# MCU_OLED.net
KiCad netlist of a schematic drawn in Altium Designer
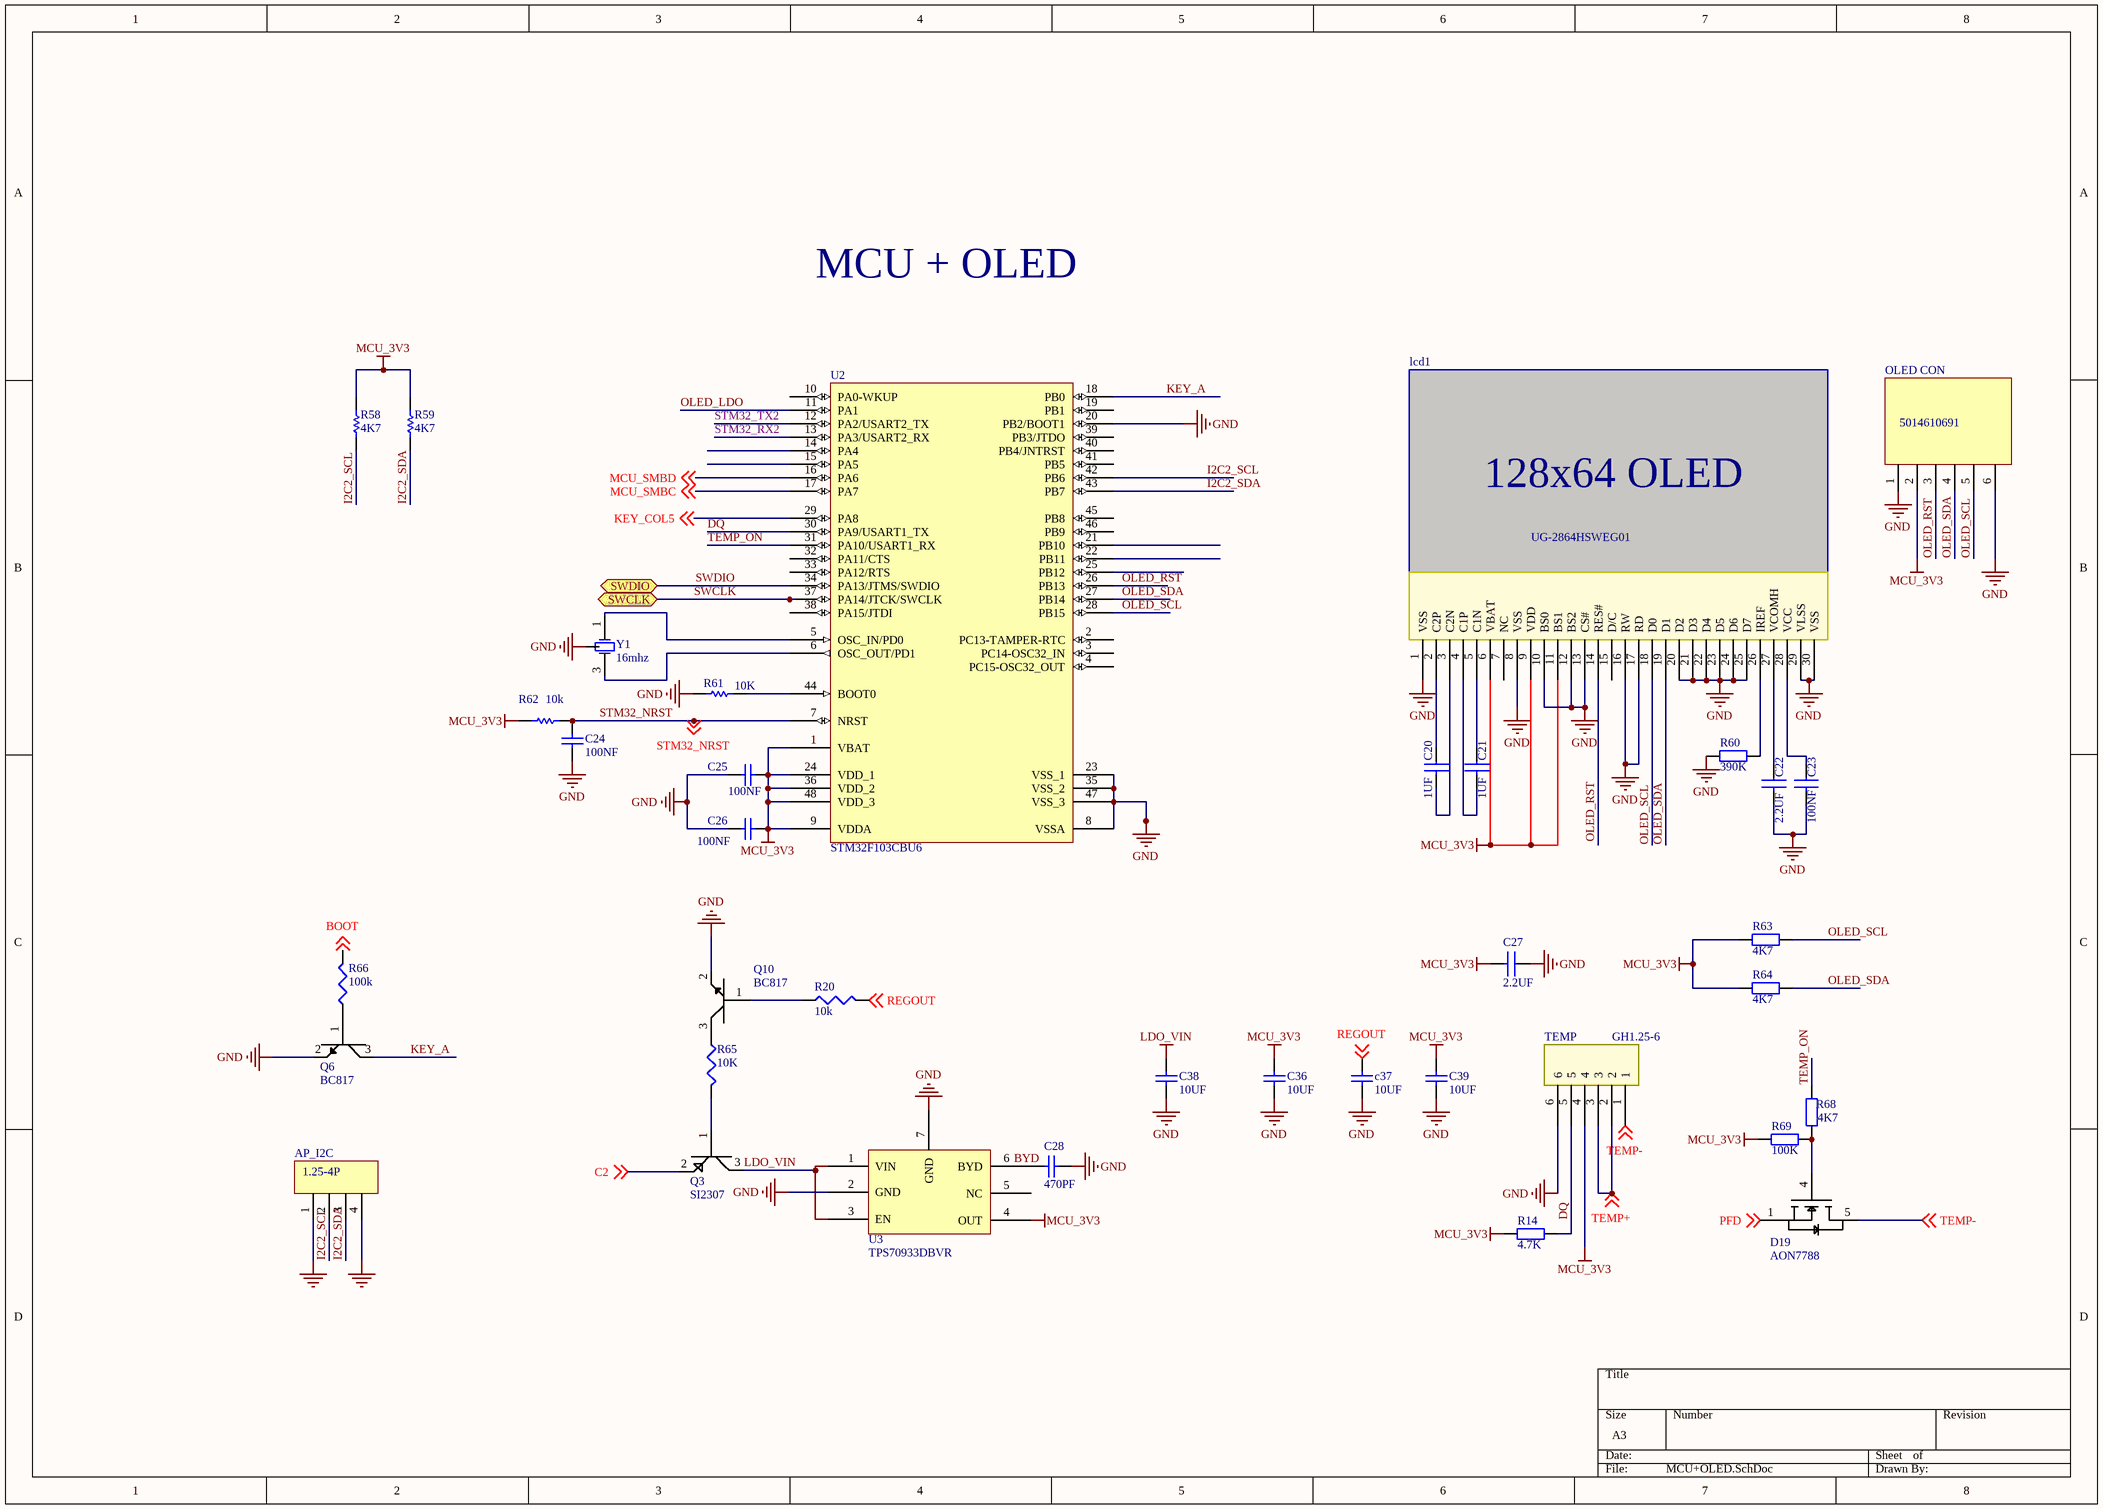
[diagram p0: MCU+OLED.SchDoc]

(export (version "E")
  (design (tool "Eeschema 10.0.6"))
  (components
    (comp (ref "AP_I2C") (value "1.25-4P") (footprint "GH1.25-4P") (libsource (lib "hack") (part "1.25-4P")))
    (comp (ref "C20")
      (value "1UF")
      (footprint "0603c")
      (description "CAP CER .10UF 50V X5R 10% 0402")
      (fields
        (field (name "MANUFACTURER") "TDK Corporation")
        (field (name "MANUFACTURER PART NUMBER") "C1005X5R1H104K")
      )
      (libsource (lib "Integrated_Library_RF_FEB_2012") (part "C1005X5R1H104K"))
    )
    (comp (ref "C21")
      (value "1UF")
      (footprint "0603c")
      (description "CAP CER .10UF 50V X5R 10% 0402")
      (fields
        (field (name "MANUFACTURER") "TDK Corporation")
        (field (name "MANUFACTURER PART NUMBER") "C1005X5R1H104K")
      )
      (libsource (lib "Integrated_Library_RF_FEB_2012") (part "C1005X5R1H104K"))
    )
    (comp (ref "C22")
      (value "2.2UF")
      (footprint "0603c")
      (description "CAP CER .10UF 50V X5R 10% 0402")
      (fields
        (field (name "MANUFACTURER") "TDK Corporation")
        (field (name "MANUFACTURER PART NUMBER") "C1005X5R1H104K")
      )
      (libsource (lib "Integrated_Library_RF_FEB_2012") (part "C1005X5R1H104K"))
    )
    (comp (ref "C23")
      (value "100NF")
      (footprint "0603c")
      (description "CAP CER .10UF 50V X5R 10% 0402")
      (fields
        (field (name "MANUFACTURER") "TDK Corporation")
        (field (name "MANUFACTURER PART NUMBER") "C1005X5R1H104K")
      )
      (libsource (lib "Integrated_Library_RF_FEB_2012") (part "C1005X5R1H104K"))
    )
    (comp (ref "C24")
      (value "100NF")
      (footprint "0402CAP")
      (description "Capacitor")
      (fields (field (name "Comment") "100nf") (field (name "PUBLISHER") "Altium Limited"))
      (libsource (lib "Miscellaneous Devices") (part "Cap"))
    )
    (comp (ref "C25")
      (value "100NF")
      (footprint "0402CAP")
      (description "Capacitor")
      (fields (field (name "Comment") "Cap") (field (name "PUBLISHER") "Altium Limited"))
      (libsource (lib "Miscellaneous Devices") (part "Cap"))
    )
    (comp (ref "C26")
      (value "100NF")
      (footprint "0402CAP")
      (description "Capacitor")
      (fields (field (name "Comment") "Cap") (field (name "PUBLISHER") "Altium Limited"))
      (libsource (lib "Miscellaneous Devices") (part "Cap"))
    )
    (comp (ref "C27")
      (value "2.2UF")
      (footprint "0603c")
      (description "CAP CER .10UF 50V X5R 10% 0402")
      (fields
        (field (name "MANUFACTURER") "TDK Corporation")
        (field (name "MANUFACTURER PART NUMBER") "C1005X5R1H104K")
      )
      (libsource (lib "Integrated_Library_RF_FEB_2012") (part "C1005X5R1H104K"))
    )
    (comp (ref "C28")
      (value "470PF")
      (description "Capacitor")
      (fields (field (name "PUBLISHER") "Altium Limited"))
      (libsource (lib "Miscellaneous Devices") (part "Cap"))
    )
    (comp (ref "C36")
      (value "10UF")
      (fields (field (name "PUBLISHER") "Altium Limited"))
      (libsource (lib "Miscellaneous Devices") (part "Cap"))
    )
    (comp (ref "c37")
      (value "10UF")
      (fields (field (name "PUBLISHER") "Altium Limited"))
      (libsource (lib "Miscellaneous Devices") (part "Cap"))
    )
    (comp (ref "C38")
      (value "10UF")
      (fields (field (name "PUBLISHER") "Altium Limited"))
      (libsource (lib "Miscellaneous Devices") (part "Cap"))
    )
    (comp (ref "C39")
      (value "10UF")
      (fields (field (name "PUBLISHER") "Altium Limited"))
      (libsource (lib "Miscellaneous Devices") (part "Cap"))
    )
    (comp (ref "D19") (value "AON7788") (footprint "DFN3x3_8L") (libsource (lib "hack") (part "AON7788")))
    (comp (ref "lcd1")
      (value "UG-2864HSWEG01")
      (footprint "1.3OLED")
      (libsource (lib "hack") (part "UG-2864HSWEG01"))
    )
    (comp (ref "OLED CON")
      (value "5014610691")
      (footprint "5014610691")
      (libsource (lib "hack") (part "5014610691"))
    )
    (comp (ref "Q3")
      (value "SI2307")
      (footprint "SOT-23 - duplicate")
      (libsource (lib "hack") (part "MMBT3906"))
    )
    (comp (ref "Q6") (value "BC817") (footprint "SOT-23 - duplicate") (libsource (lib "hack") (part "BC718")))
    (comp (ref "Q10")
      (value "BC817")
      (footprint "SOT-23 - duplicate")
      (libsource (lib "hack") (part "BC718"))
    )
    (comp (ref "R14")
      (value "4.7K")
      (description "Resistor")
      (fields (field (name "PUBLISHER") "Altium Limited"))
      (libsource (lib "Miscellaneous Devices") (part "Res2"))
    )
    (comp (ref "R20")
      (value "10k")
      (footprint "0402R")
      (description "RES TF 4.99K OHM 1% 1/16W 0402")
      (fields
        (field (name "MANUFACTURER") "Stackpole Electronics Inc")
        (field (name "MANUFACTURER PART NUMBER") "RMCF0402FT4K99")
      )
      (libsource (lib "Integrated_Library_RF_FEB_2012") (part "RMCF0402FT4K99"))
    )
    (comp (ref "R58")
      (value "4K7")
      (footprint "0402R")
      (description "Semiconductor Resistor")
      (fields (field (name "PUBLISHER") "Altium Limited"))
      (libsource (lib "Miscellaneous Devices") (part "Res Semi"))
    )
    (comp (ref "R59")
      (value "4K7")
      (footprint "0402R")
      (description "Semiconductor Resistor")
      (fields (field (name "PUBLISHER") "Altium Limited"))
      (libsource (lib "Miscellaneous Devices") (part "Res Semi"))
    )
    (comp (ref "R60")
      (value "390K")
      (description "Resistor")
      (fields (field (name "PUBLISHER") "Altium Limited"))
      (libsource (lib "Miscellaneous Devices") (part "Res2"))
    )
    (comp (ref "R61")
      (value "10K")
      (footprint "0402R")
      (description "Semiconductor Resistor")
      (fields (field (name "PUBLISHER") "Altium Limited"))
      (libsource (lib "Miscellaneous Devices") (part "Res Semi"))
    )
    (comp (ref "R62")
      (value "10k")
      (footprint "0402R")
      (description "Semiconductor Resistor")
      (fields (field (name "PUBLISHER") "Altium Limited"))
      (libsource (lib "Miscellaneous Devices") (part "Res Semi"))
    )
    (comp (ref "R63")
      (value "4K7")
      (description "Resistor")
      (fields (field (name "PUBLISHER") "Altium Limited"))
      (libsource (lib "Miscellaneous Devices") (part "Res2"))
    )
    (comp (ref "R64")
      (value "4K7")
      (description "Resistor")
      (fields (field (name "PUBLISHER") "Altium Limited"))
      (libsource (lib "Miscellaneous Devices") (part "Res2"))
    )
    (comp (ref "R65")
      (value "10K")
      (footprint "0402r")
      (description "RES TF 4.99K OHM 1% 1/16W 0402")
      (fields
        (field (name "MANUFACTURER") "Stackpole Electronics Inc")
        (field (name "MANUFACTURER PART NUMBER") "RMCF0402FT4K99")
      )
      (libsource (lib "Integrated_Library_RF_FEB_2012") (part "RMCF0402FT4K99"))
    )
    (comp (ref "R66")
      (value "100k")
      (footprint "0402r")
      (description "RES TF 4.99K OHM 1% 1/16W 0402")
      (fields
        (field (name "MANUFACTURER") "Stackpole Electronics Inc")
        (field (name "MANUFACTURER PART NUMBER") "RMCF0402FT4K99")
      )
      (libsource (lib "Integrated_Library_RF_FEB_2012") (part "RMCF0402FT4K99"))
    )
    (comp (ref "R68")
      (value "4K7")
      (description "Resistor")
      (fields (field (name "PUBLISHER") "Altium Limited"))
      (libsource (lib "") (part "Res2_1"))
    )
    (comp (ref "R69")
      (value "100K")
      (description "Resistor")
      (fields (field (name "PUBLISHER") "Altium Limited"))
      (libsource (lib "") (part "Res2_2"))
    )
    (comp (ref "TEMP") (value "GH1.25-6") (footprint "GH1.25-6") (libsource (lib "hack") (part "GH1.25-6")))
    (comp (ref "U2")
      (value "STM32F103CBU6")
      (footprint "QFN48")
      (description "STM32 ARM-based 32-bit MCU with 64 Kbytes Flash, 48-pin LQFP, Industrial Temperature")
      (fields (field (name "PUBLISHER") "Altium Limited"))
      (libsource (lib "ST Microcontroller 32-Bit STM32") (part "STM32F103C8T6"))
    )
    (comp (ref "U3") (value "TPS70933DBVR") (footprint "MLF-6") (libsource (lib "hack") (part "MIC5219-3V3")))
    (comp (ref "Y1")
      (value "16mhz")
      (footprint "RESONATOR")
      (description "Crystal Oscillator")
      (fields (field (name "PUBLISHER") "Altium Limited"))
      (libsource (lib "Miscellaneous Devices") (part "XTAL"))
    )
  )
  (nets
    (net (code "2") (name "/DQ") (class "Default")
      (node (ref "R14") (pin "2") (pinfunction "2_2") (pintype "passive"))
      (node (ref "TEMP") (pin "5") (pinfunction "5_5") (pintype "passive"))
      (node (ref "U2") (pin "30") (pinfunction "PA9/USART1_TX_30") (pintype "bidirectional"))
    )
    (net (code "3") (name "/I2C2_SCL") (class "Default")
      (node (ref "AP_I2C") (pin "2") (pintype "passive"))
      (node (ref "R58") (pin "2") (pinfunction "2_2") (pintype "passive"))
      (node (ref "U2") (pin "42") (pinfunction "PB6_42") (pintype "bidirectional"))
    )
    (net (code "4") (name "/I2C2_SDA") (class "Default")
      (node (ref "AP_I2C") (pin "3") (pintype "passive"))
      (node (ref "R59") (pin "2") (pinfunction "2_2") (pintype "passive"))
      (node (ref "U2") (pin "43") (pinfunction "PB7_43") (pintype "bidirectional"))
    )
    (net (code "5") (name "/KEY_A") (class "Default")
      (node (ref "Q6") (pin "3") (pinfunction "collector_3") (pintype "passive"))
      (node (ref "U2") (pin "18") (pinfunction "PB0_18") (pintype "bidirectional"))
    )
    (net (code "6") (name "/OLED_LDO") (class "Default")
      (node (ref "U2") (pin "11") (pinfunction "PA1_11") (pintype "bidirectional"))
    )
    (net (code "7") (name "/OLED_RST") (class "Default")
      (node (ref "OLED CON") (pin "3") (pintype "passive"))
      (node (ref "U2") (pin "26") (pinfunction "PB13_26") (pintype "bidirectional"))
      (node (ref "lcd1") (pin "14") (pinfunction "RES#_14") (pintype "passive"))
    )
    (net (code "8") (name "/OLED_SCL") (class "Default")
      (node (ref "OLED CON") (pin "5") (pintype "passive"))
      (node (ref "R63") (pin "2") (pinfunction "2_2") (pintype "passive"))
      (node (ref "U2") (pin "28") (pinfunction "PB15_28") (pintype "bidirectional"))
      (node (ref "lcd1") (pin "18") (pinfunction "D0_18") (pintype "passive"))
    )
    (net (code "9") (name "/OLED_SDA") (class "Default")
      (node (ref "OLED CON") (pin "4") (pintype "passive"))
      (node (ref "R64") (pin "2") (pinfunction "2_2") (pintype "passive"))
      (node (ref "U2") (pin "27") (pinfunction "PB14_27") (pintype "bidirectional"))
      (node (ref "lcd1") (pin "19") (pinfunction "D1_19") (pintype "passive"))
    )
    (net (code "10") (name "/STM32_RX2") (class "Default")
      (node (ref "U2") (pin "13") (pinfunction "PA3/USART2_RX_13") (pintype "bidirectional"))
    )
    (net (code "11") (name "/STM32_TX2") (class "Default")
      (node (ref "U2") (pin "12") (pinfunction "PA2/USART2_TX_12") (pintype "bidirectional"))
    )
    (net (code "12") (name "/SWCLK") (class "Default")
      (node (ref "U2") (pin "37") (pinfunction "PA14/JTCK/SWCLK_37") (pintype "bidirectional"))
    )
    (net (code "13") (name "/SWDIO") (class "Default")
      (node (ref "U2") (pin "34") (pinfunction "PA13/JTMS/SWDIO_34") (pintype "bidirectional"))
    )
    (net (code "14") (name "/TEMP_ON") (class "Default")
      (node (ref "R68") (pin "2") (pinfunction "2_2") (pintype "passive"))
      (node (ref "U2") (pin "31") (pinfunction "PA10/USART1_RX_31") (pintype "bidirectional"))
    )
    (net (code "15") (name "BOOT") (class "Default")
      (node (ref "R66") (pin "2") (pinfunction "2_2") (pintype "passive"))
    )
    (net (code "16") (name "C2") (class "Default")
      (node (ref "Q3") (pin "2") (pinfunction "emitter_2") (pintype "passive"))
    )
    (net (code "17") (name "GND") (class "Default")
      (node (ref "AP_I2C") (pin "1") (pintype "passive"))
      (node (ref "AP_I2C") (pin "4") (pintype "passive"))
      (node (ref "C22") (pin "2") (pinfunction "2_2") (pintype "passive"))
      (node (ref "C23") (pin "2") (pinfunction "2_2") (pintype "passive"))
      (node (ref "C24") (pin "2") (pinfunction "2_2") (pintype "passive"))
      (node (ref "C25") (pin "1") (pinfunction "1_1") (pintype "passive"))
      (node (ref "C26") (pin "1") (pinfunction "1_1") (pintype "passive"))
      (node (ref "C27") (pin "1") (pinfunction "1_1") (pintype "passive"))
      (node (ref "C28") (pin "2") (pinfunction "2_2") (pintype "passive"))
      (node (ref "C36") (pin "1") (pinfunction "1_1") (pintype "passive"))
      (node (ref "C38") (pin "1") (pinfunction "1_1") (pintype "passive"))
      (node (ref "C39") (pin "1") (pinfunction "1_1") (pintype "passive"))
      (node (ref "OLED CON") (pin "1") (pintype "passive"))
      (node (ref "OLED CON") (pin "6") (pintype "passive"))
      (node (ref "Q10") (pin "2") (pinfunction "emitter_2") (pintype "passive"))
      (node (ref "Q6") (pin "2") (pinfunction "emitter_2") (pintype "passive"))
      (node (ref "R60") (pin "1") (pinfunction "1_1") (pintype "passive"))
      (node (ref "R61") (pin "2") (pinfunction "2_2") (pintype "passive"))
      (node (ref "TEMP") (pin "6") (pinfunction "6_6") (pintype "passive"))
      (node (ref "U2") (pin "20") (pinfunction "PB2/BOOT1_20") (pintype "bidirectional"))
      (node (ref "U2") (pin "23") (pinfunction "VSS_1_23") (pintype "power_in"))
      (node (ref "U2") (pin "35") (pinfunction "VSS_2_35") (pintype "power_in"))
      (node (ref "U2") (pin "47") (pinfunction "VSS_3_47") (pintype "power_in"))
      (node (ref "U2") (pin "8") (pinfunction "VSSA_8") (pintype "power_in"))
      (node (ref "U3") (pin "2") (pinfunction "GND_2") (pintype "passive"))
      (node (ref "U3") (pin "7") (pinfunction "GND_7") (pintype "passive"))
      (node (ref "Y1") (pin "2") (pinfunction "GND_2") (pintype "passive"))
      (node (ref "c37") (pin "1") (pinfunction "1_1") (pintype "passive"))
      (node (ref "lcd1") (pin "1") (pinfunction "VSS_1") (pintype "passive"))
      (node (ref "lcd1") (pin "10") (pinfunction "BS0_10") (pintype "passive"))
      (node (ref "lcd1") (pin "12") (pinfunction "BS2_12") (pintype "passive"))
      (node (ref "lcd1") (pin "13") (pinfunction "CS#_13") (pintype "passive"))
      (node (ref "lcd1") (pin "16") (pinfunction "RW_16") (pintype "passive"))
      (node (ref "lcd1") (pin "17") (pinfunction "RD_17") (pintype "passive"))
      (node (ref "lcd1") (pin "20") (pinfunction "D2_20") (pintype "passive"))
      (node (ref "lcd1") (pin "21") (pinfunction "D3_21") (pintype "passive"))
      (node (ref "lcd1") (pin "22") (pinfunction "D4_22") (pintype "passive"))
      (node (ref "lcd1") (pin "23") (pinfunction "D5_23") (pintype "passive"))
      (node (ref "lcd1") (pin "24") (pinfunction "D6_24") (pintype "passive"))
      (node (ref "lcd1") (pin "25") (pinfunction "D7_25") (pintype "passive"))
      (node (ref "lcd1") (pin "29") (pinfunction "VLSS_29") (pintype "passive"))
      (node (ref "lcd1") (pin "30") (pinfunction "VSS_30") (pintype "passive"))
      (node (ref "lcd1") (pin "8") (pinfunction "VSS_8") (pintype "passive"))
    )
    (net (code "18") (name "KEY_COL5") (class "Default")
      (node (ref "U2") (pin "29") (pinfunction "PA8_29") (pintype "bidirectional"))
    )
    (net (code "19") (name "LDO_VIN") (class "Default")
      (node (ref "C38") (pin "2") (pinfunction "2_2") (pintype "passive"))
      (node (ref "Q3") (pin "3") (pinfunction "collector_3") (pintype "passive"))
      (node (ref "U3") (pin "1") (pinfunction "VIN_1") (pintype "passive"))
      (node (ref "U3") (pin "3") (pinfunction "EN_3") (pintype "passive"))
    )
    (net (code "20") (name "MCU_3V3") (class "Default")
      (node (ref "C25") (pin "2") (pinfunction "2_2") (pintype "passive"))
      (node (ref "C26") (pin "2") (pinfunction "2_2") (pintype "passive"))
      (node (ref "C27") (pin "2") (pinfunction "2_2") (pintype "passive"))
      (node (ref "C36") (pin "2") (pinfunction "2_2") (pintype "passive"))
      (node (ref "C39") (pin "2") (pinfunction "2_2") (pintype "passive"))
      (node (ref "OLED CON") (pin "2") (pintype "passive"))
      (node (ref "R14") (pin "1") (pinfunction "1_1") (pintype "passive"))
      (node (ref "R58") (pin "1") (pinfunction "1_1") (pintype "passive"))
      (node (ref "R59") (pin "1") (pinfunction "1_1") (pintype "passive"))
      (node (ref "R62") (pin "2") (pinfunction "2_2") (pintype "passive"))
      (node (ref "R63") (pin "1") (pinfunction "1_1") (pintype "passive"))
      (node (ref "R64") (pin "1") (pinfunction "1_1") (pintype "passive"))
      (node (ref "R69") (pin "2") (pinfunction "2_2") (pintype "passive"))
      (node (ref "TEMP") (pin "4") (pinfunction "4_4") (pintype "passive"))
      (node (ref "U2") (pin "1") (pinfunction "VBAT_1") (pintype "power_in"))
      (node (ref "U2") (pin "24") (pinfunction "VDD_1_24") (pintype "power_in"))
      (node (ref "U2") (pin "36") (pinfunction "VDD_2_36") (pintype "power_in"))
      (node (ref "U2") (pin "48") (pinfunction "VDD_3_48") (pintype "power_in"))
      (node (ref "U2") (pin "9") (pinfunction "VDDA_9") (pintype "power_in"))
      (node (ref "U3") (pin "4") (pinfunction "OUT_4") (pintype "passive"))
      (node (ref "lcd1") (pin "11") (pinfunction "BS1_11") (pintype "passive"))
      (node (ref "lcd1") (pin "6") (pinfunction "VBAT_6") (pintype "passive"))
      (node (ref "lcd1") (pin "9") (pinfunction "VDD_9") (pintype "passive"))
    )
    (net (code "21") (name "MCU_SMBC") (class "Default")
      (node (ref "U2") (pin "17") (pinfunction "PA7_17") (pintype "bidirectional"))
    )
    (net (code "22") (name "MCU_SMBD") (class "Default")
      (node (ref "U2") (pin "16") (pinfunction "PA6_16") (pintype "bidirectional"))
    )
    (net (code "23") (name "Net-(D19-G)") (class "Default")
      (node (ref "D19") (pin "4") (pinfunction "G_4") (pintype "passive"))
      (node (ref "R68") (pin "1") (pinfunction "1_1") (pintype "passive"))
      (node (ref "R69") (pin "1") (pinfunction "1_1") (pintype "passive"))
    )
    (net (code "24") (name "Net-(Q3-base)") (class "Default")
      (node (ref "Q3") (pin "1") (pinfunction "base_1") (pintype "passive"))
      (node (ref "R65") (pin "2") (pinfunction "2_2") (pintype "passive"))
    )
    (net (code "25") (name "Net-(Q6-base)") (class "Default")
      (node (ref "Q6") (pin "1") (pinfunction "base_1") (pintype "passive"))
      (node (ref "R66") (pin "1") (pinfunction "1_1") (pintype "passive"))
    )
    (net (code "26") (name "Net-(Q10-base)") (class "Default")
      (node (ref "Q10") (pin "1") (pinfunction "base_1") (pintype "passive"))
      (node (ref "R20") (pin "1") (pinfunction "1_1") (pintype "passive"))
    )
    (net (code "27") (name "Net-(Q10-collector)") (class "Default")
      (node (ref "Q10") (pin "3") (pinfunction "collector_3") (pintype "passive"))
      (node (ref "R65") (pin "1") (pinfunction "1_1") (pintype "passive"))
    )
    (net (code "28") (name "Net-(U2-BOOT0)") (class "Default")
      (node (ref "R61") (pin "1") (pinfunction "1_1") (pintype "passive"))
      (node (ref "U2") (pin "44") (pinfunction "BOOT0_44") (pintype "input"))
    )
    (net (code "29") (name "Net-(U2-OSC_IN{slash}PD0)") (class "Default")
      (node (ref "U2") (pin "5") (pinfunction "OSC_IN/PD0_5") (pintype "input"))
      (node (ref "Y1") (pin "1") (pinfunction "OSC1_1") (pintype "passive"))
    )
    (net (code "30") (name "Net-(U2-OSC_OUT{slash}PD1)") (class "Default")
      (node (ref "U2") (pin "6") (pinfunction "OSC_OUT/PD1_6") (pintype "output"))
      (node (ref "Y1") (pin "3") (pinfunction "OSC2_3") (pintype "passive"))
    )
    (net (code "31") (name "Net-(U3-BYD)") (class "Default")
      (node (ref "C28") (pin "1") (pinfunction "1_1") (pintype "passive"))
      (node (ref "U3") (pin "6") (pinfunction "BYD_6") (pintype "passive"))
    )
    (net (code "32") (name "Net-(lcd1-C1N)") (class "Default")
      (node (ref "C21") (pin "1") (pinfunction "1_1") (pintype "passive"))
      (node (ref "lcd1") (pin "5") (pinfunction "C1N_5") (pintype "passive"))
    )
    (net (code "33") (name "Net-(lcd1-C1P)") (class "Default")
      (node (ref "C21") (pin "2") (pinfunction "2_2") (pintype "passive"))
      (node (ref "lcd1") (pin "4") (pinfunction "C1P_4") (pintype "passive"))
    )
    (net (code "34") (name "Net-(lcd1-C2N)") (class "Default")
      (node (ref "C20") (pin "2") (pinfunction "2_2") (pintype "passive"))
      (node (ref "lcd1") (pin "3") (pinfunction "C2N_3") (pintype "passive"))
    )
    (net (code "35") (name "Net-(lcd1-C2P)") (class "Default")
      (node (ref "C20") (pin "1") (pinfunction "1_1") (pintype "passive"))
      (node (ref "lcd1") (pin "2") (pinfunction "C2P_2") (pintype "passive"))
    )
    (net (code "36") (name "Net-(lcd1-IREF)") (class "Default")
      (node (ref "R60") (pin "2") (pinfunction "2_2") (pintype "passive"))
      (node (ref "lcd1") (pin "26") (pinfunction "IREF_26") (pintype "passive"))
    )
    (net (code "37") (name "Net-(lcd1-VCC)") (class "Default")
      (node (ref "C23") (pin "1") (pinfunction "1_1") (pintype "passive"))
      (node (ref "lcd1") (pin "28") (pinfunction "VCC_28") (pintype "passive"))
    )
    (net (code "38") (name "Net-(lcd1-VCOMH)") (class "Default")
      (node (ref "C22") (pin "1") (pinfunction "1_1") (pintype "passive"))
      (node (ref "lcd1") (pin "27") (pinfunction "VCOMH_27") (pintype "passive"))
    )
    (net (code "39") (name "PFD") (class "Default")
      (node (ref "D19") (pin "1") (pinfunction "S_1") (pintype "passive"))
    )
    (net (code "40") (name "REGOUT") (class "Default")
      (node (ref "R20") (pin "2") (pinfunction "2_2") (pintype "passive"))
      (node (ref "c37") (pin "2") (pinfunction "2_2") (pintype "passive"))
    )
    (net (code "41") (name "STM32_NRST") (class "Default")
      (node (ref "C24") (pin "1") (pinfunction "1_1") (pintype "passive"))
      (node (ref "R62") (pin "1") (pinfunction "1_1") (pintype "passive"))
      (node (ref "U2") (pin "7") (pinfunction "NRST_7") (pintype "bidirectional"))
    )
    (net (code "42") (name "TEMP+") (class "Default")
      (node (ref "TEMP") (pin "2") (pinfunction "2_2") (pintype "passive"))
      (node (ref "TEMP") (pin "3") (pinfunction "3_3") (pintype "passive"))
    )
    (net (code "43") (name "TEMP-") (class "Default")
      (node (ref "D19") (pin "5") (pinfunction "D_5") (pintype "passive"))
      (node (ref "TEMP") (pin "1") (pinfunction "1_1") (pintype "passive"))
    )
    (net (code "44") (name "unconnected-(U2-PA0-WKUP-Pad10)") (class "Default")
      (node (ref "U2") (pin "10") (pinfunction "PA0-WKUP_10") (pintype "bidirectional"))
    )
    (net (code "45") (name "unconnected-(U2-PA4-Pad14)") (class "Default")
      (node (ref "U2") (pin "14") (pinfunction "PA4_14") (pintype "bidirectional"))
    )
    (net (code "46") (name "unconnected-(U2-PA5-Pad15)") (class "Default")
      (node (ref "U2") (pin "15") (pinfunction "PA5_15") (pintype "bidirectional"))
    )
    (net (code "47") (name "unconnected-(U2-PA11{slash}CTS-Pad32)") (class "Default")
      (node (ref "U2") (pin "32") (pinfunction "PA11/CTS_32") (pintype "bidirectional"))
    )
    (net (code "48") (name "unconnected-(U2-PA12{slash}RTS-Pad33)") (class "Default")
      (node (ref "U2") (pin "33") (pinfunction "PA12/RTS_33") (pintype "bidirectional"))
    )
    (net (code "49") (name "unconnected-(U2-PA15{slash}JTDI-Pad38)") (class "Default")
      (node (ref "U2") (pin "38") (pinfunction "PA15/JTDI_38") (pintype "bidirectional"))
    )
    (net (code "50") (name "unconnected-(U2-PB1-Pad19)") (class "Default")
      (node (ref "U2") (pin "19") (pinfunction "PB1_19") (pintype "bidirectional"))
    )
    (net (code "51") (name "unconnected-(U2-PB3{slash}JTDO-Pad39)") (class "Default")
      (node (ref "U2") (pin "39") (pinfunction "PB3/JTDO_39") (pintype "bidirectional"))
    )
    (net (code "52") (name "unconnected-(U2-PB4{slash}JNTRST-Pad40)") (class "Default")
      (node (ref "U2") (pin "40") (pinfunction "PB4/JNTRST_40") (pintype "bidirectional"))
    )
    (net (code "53") (name "unconnected-(U2-PB5-Pad41)") (class "Default")
      (node (ref "U2") (pin "41") (pinfunction "PB5_41") (pintype "bidirectional"))
    )
    (net (code "54") (name "unconnected-(U2-PB8-Pad45)") (class "Default")
      (node (ref "U2") (pin "45") (pinfunction "PB8_45") (pintype "bidirectional"))
    )
    (net (code "55") (name "unconnected-(U2-PB9-Pad46)") (class "Default")
      (node (ref "U2") (pin "46") (pinfunction "PB9_46") (pintype "bidirectional"))
    )
    (net (code "56") (name "unconnected-(U2-PB10-Pad21)") (class "Default")
      (node (ref "U2") (pin "21") (pinfunction "PB10_21") (pintype "bidirectional"))
    )
    (net (code "57") (name "unconnected-(U2-PB11-Pad22)") (class "Default")
      (node (ref "U2") (pin "22") (pinfunction "PB11_22") (pintype "bidirectional"))
    )
    (net (code "58") (name "unconnected-(U2-PB12-Pad25)") (class "Default")
      (node (ref "U2") (pin "25") (pinfunction "PB12_25") (pintype "bidirectional"))
    )
    (net (code "59") (name "unconnected-(U2-PC13-TAMPER-RTC-Pad2)") (class "Default")
      (node (ref "U2") (pin "2") (pinfunction "PC13-TAMPER-RTC_2") (pintype "bidirectional"))
    )
    (net (code "60") (name "unconnected-(U2-PC14-OSC32_IN-Pad3)") (class "Default")
      (node (ref "U2") (pin "3") (pinfunction "PC14-OSC32_IN_3") (pintype "bidirectional"))
    )
    (net (code "61") (name "unconnected-(U2-PC15-OSC32_OUT-Pad4)") (class "Default")
      (node (ref "U2") (pin "4") (pinfunction "PC15-OSC32_OUT_4") (pintype "bidirectional"))
    )
    (net (code "62") (name "unconnected-(U3-NC-Pad5)") (class "Default")
      (node (ref "U3") (pin "5") (pinfunction "NC_5") (pintype "passive"))
    )
    (net (code "63") (name "unconnected-(lcd1-D{slash}C-Pad15)") (class "Default")
      (node (ref "lcd1") (pin "15") (pinfunction "D/C_15") (pintype "passive"))
    )
    (net (code "64") (name "unconnected-(lcd1-NC-Pad7)") (class "Default")
      (node (ref "lcd1") (pin "7") (pinfunction "NC_7") (pintype "passive"))
    )
  )
)
